# AT89S52.net
KiCad netlist of a schematic drawn in Altium Designer
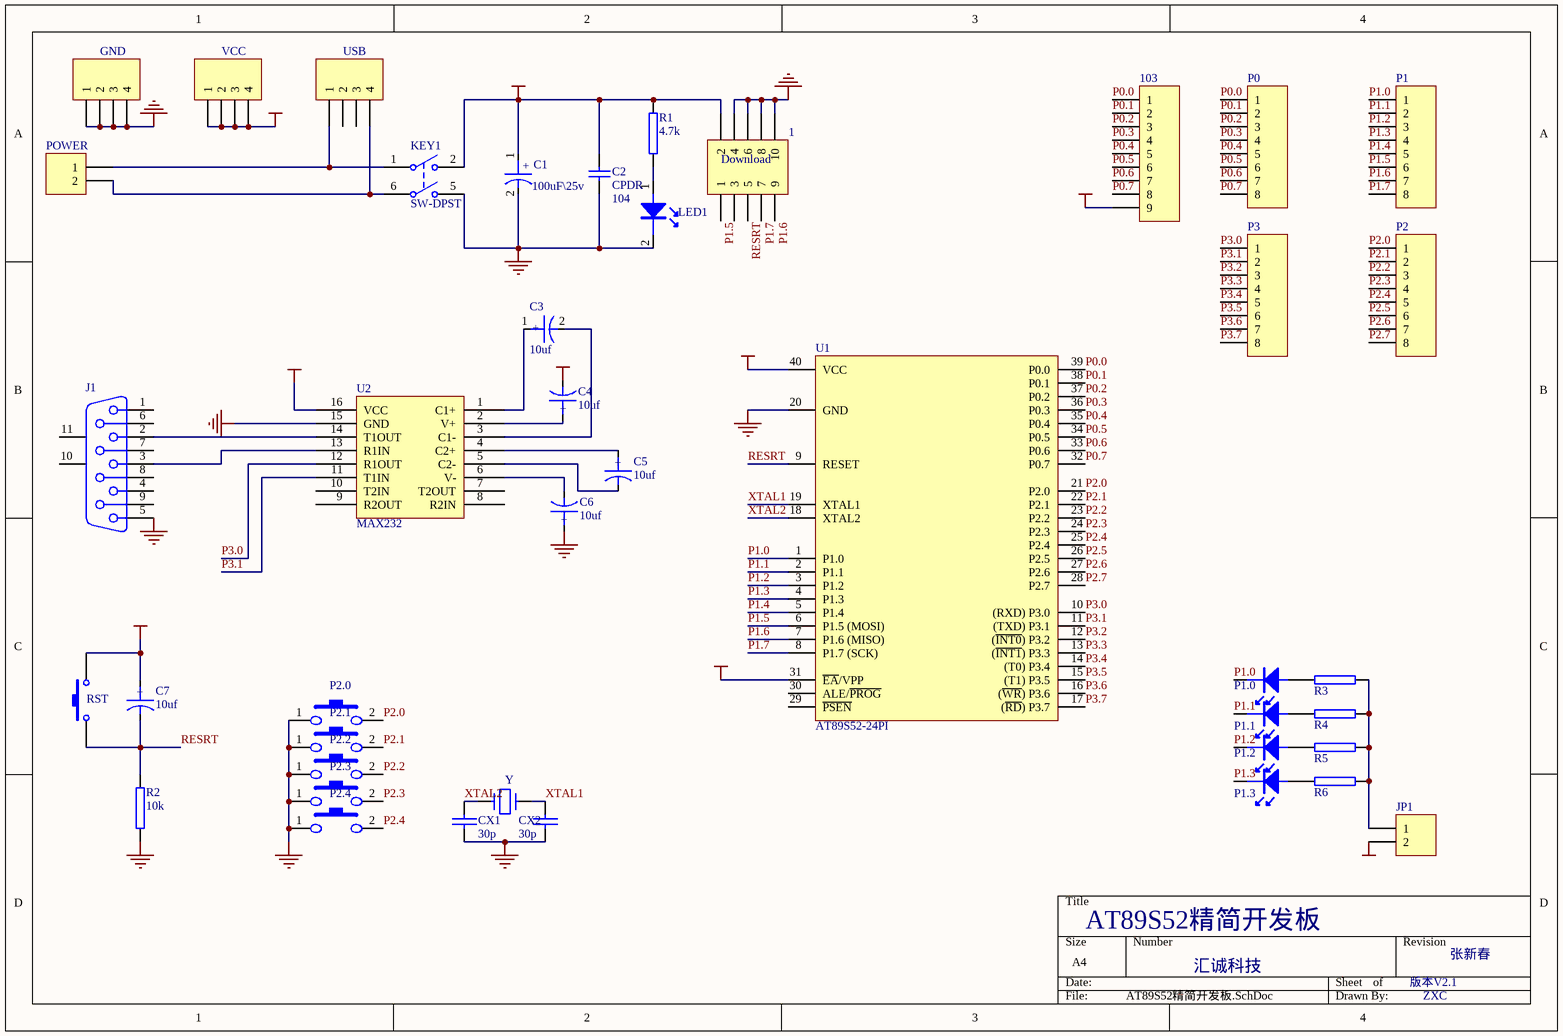
[diagram p0: AT89S52精简开发板.SchDoc]

(export (version "E")
  (design (tool "Eeschema 10.0.6"))
  (components
    (comp (ref "1")
      (value "Download")
      (footprint "HDR-2x5")
      (description "Header, 5-Pin, Dual row")
      (fields (field (name "PUBLISHER") "Altium Limited"))
      (libsource (lib "Miscellaneous Connectors") (part "Header 5X2"))
    )
    (comp (ref "103")
      (value "~")
      (footprint "HDR-9")
      (description "排针——9")
      (fields (field (name "PUBLISHER") "Altium Limited"))
      (libsource (lib "zxcourhc") (part "PZ_9"))
    )
    (comp (ref "C1")
      (value "100u~{F}25v")
      (footprint "C-DJ-6")
      (description "Capacitor")
      (libsource (lib "OldCow1 (1)") (part "CAPACITOR POL"))
    )
    (comp (ref "C2")
      (value "CPDR")
      (footprint "CPDR")
      (description "瓷片电容")
      (fields (field (name "ALTIUM_VALUE") "104") (field (name "PUBLISHER") "Altium Limited"))
      (libsource (lib "zxcourhc") (part "CPDR"))
    )
    (comp (ref "C3")
      (value "10uf")
      (footprint "C-DJ-4")
      (description "Capacitor")
      (libsource (lib "") (part "CAPACITOR POL_1"))
    )
    (comp (ref "C4")
      (value "10uf")
      (footprint "C-DJ-4")
      (description "Capacitor")
      (libsource (lib "*") (part "CAPACITOR POL"))
    )
    (comp (ref "C5")
      (value "10uf")
      (footprint "C-DJ-4")
      (description "Capacitor")
      (libsource (lib "*") (part "CAPACITOR POL"))
    )
    (comp (ref "C6")
      (value "10uf")
      (footprint "C-DJ-4")
      (description "Capacitor")
      (libsource (lib "*") (part "CAPACITOR POL"))
    )
    (comp (ref "C7")
      (value "10uf")
      (footprint "C-DJ-4")
      (description "Capacitor")
      (libsource (lib "*") (part "CAPACITOR POL"))
    )
    (comp (ref "CX1")
      (value "30p")
      (footprint "HDR1X2")
      (description "Capacitor")
      (libsource (lib "*") (part "CAP"))
    )
    (comp (ref "CX2")
      (value "30p")
      (footprint "HDR1X2")
      (description "Capacitor")
      (libsource (lib "*") (part "CAP"))
    )
    (comp (ref "GND")
      (value "~")
      (footprint "HDR1X4")
      (description "Header, 4-Pin")
      (fields (field (name "PUBLISHER") "Altium Limited"))
      (libsource (lib "Miscellaneous Connectors") (part "Header 4"))
    )
    (comp (ref "J1")
      (value "D Connector 9")
      (footprint "DSUB1.385-2H9")
      (description "Receptacle Assembly, 9 Position, Right Angle")
      (fields (field (name "PUBLISHER") "Altium Limited"))
      (libsource (lib "Miscellaneous Connectors") (part "D Connector 9"))
    )
    (comp (ref "JP1")
      (value "~")
      (footprint "HDR1X2")
      (description "Header, 2-Pin")
      (fields (field (name "PUBLISHER") "Altium Limited"))
      (libsource (lib "") (part "Header 2_1"))
    )
    (comp (ref "KEY1")
      (value "SW-DPST")
      (footprint "DPDT-6")
      (description "Double-Pole, Single-Throw Switch")
      (fields (field (name "PUBLISHER") "Altium Limited"))
      (libsource (lib "Miscellaneous Devices") (part "SW-DPST"))
    )
    (comp (ref "LED1") (value "LED") (footprint "LED") (libsource (lib "") (part "LED_1")))
    (comp (ref "P0")
      (value "~")
      (footprint "HDR-8")
      (description "排针——8")
      (fields (field (name "PUBLISHER") "Altium Limited"))
      (libsource (lib "zxcourhc") (part "PZ_8"))
    )
    (comp (ref "P1")
      (value "~")
      (footprint "HDR-8")
      (description "排针——8")
      (fields (field (name "PUBLISHER") "Altium Limited"))
      (libsource (lib "zxcourhc") (part "PZ_8"))
    )
    (comp (ref "P1.0") (value "LED") (footprint "HDR1X2") (libsource (lib "OldCow1 (1)") (part "LED")))
    (comp (ref "P1.1") (value "LED") (footprint "HDR1X2") (libsource (lib "OldCow1 (1)") (part "LED")))
    (comp (ref "P1.2") (value "LED") (footprint "HDR1X2") (libsource (lib "OldCow1 (1)") (part "LED")))
    (comp (ref "P1.3") (value "LED") (footprint "HDR1X2") (libsource (lib "OldCow1 (1)") (part "LED")))
    (comp (ref "P2")
      (value "~")
      (footprint "HDR-8")
      (description "排针——8")
      (fields (field (name "PUBLISHER") "Altium Limited"))
      (libsource (lib "zxcourhc") (part "PZ_8"))
    )
    (comp (ref "P2.0") (value "key1") (footprint "an-6*6") (libsource (lib "OldCow1 (1)") (part "key")))
    (comp (ref "P2.1") (value "key2") (footprint "an-6*6") (libsource (lib "OldCow1 (1)") (part "key")))
    (comp (ref "P2.2") (value "key3") (footprint "an-6*6") (libsource (lib "OldCow1 (1)") (part "key")))
    (comp (ref "P2.3") (value "key4") (footprint "an-6*6") (libsource (lib "OldCow1 (1)") (part "key")))
    (comp (ref "P2.4") (value "key4") (footprint "an-6*6") (libsource (lib "OldCow1 (1)") (part "key")))
    (comp (ref "P3")
      (value "~")
      (footprint "HDR-8")
      (description "排针——8")
      (fields (field (name "PUBLISHER") "Altium Limited"))
      (libsource (lib "zxcourhc") (part "PZ_8"))
    )
    (comp (ref "POWER")
      (value "~")
      (footprint "JK128")
      (description "Header, 2-Pin")
      (fields (field (name "PUBLISHER") "Altium Limited"))
      (libsource (lib "Miscellaneous Connectors") (part "Header 2"))
    )
    (comp (ref "R1") (value "4.7k") (footprint "RSE") (libsource (lib "*") (part "RES2")))
    (comp (ref "R2") (value "10k") (footprint "RSE") (libsource (lib "*") (part "RES2")))
    (comp (ref "R3") (value "470") (footprint "RSE") (libsource (lib "*") (part "RES2")))
    (comp (ref "R4") (value "470") (footprint "RSE") (libsource (lib "*") (part "RES2")))
    (comp (ref "R5") (value "470") (footprint "RSE") (libsource (lib "*") (part "RES2")))
    (comp (ref "R6") (value "470") (footprint "RSE") (libsource (lib "*") (part "RES2")))
    (comp (ref "RST")
      (value "~")
      (footprint "an-6*6")
      (description "Switch")
      (fields (field (name "PUBLISHER") "Altium Limited"))
      (libsource (lib "Miscellaneous Devices") (part "SW-PB"))
    )
    (comp (ref "U1")
      (value "AT89S52-24PI")
      (footprint "DIP-40")
      (description "8 位微处理器/40引脚")
      (fields (field (name "发布者") "磊元工作室"))
      (libsource (lib "MCU") (part "AT89S52-P"))
    )
    (comp (ref "U2") (value "MAX232") (footprint "DIP16") (libsource (lib "*") (part "MAX232")))
    (comp (ref "USB")
      (value "~")
      (footprint "USB-5V")
      (description "Header, 4-Pin")
      (fields (field (name "PUBLISHER") "Altium Limited"))
      (libsource (lib "Miscellaneous Connectors") (part "Header 4"))
    )
    (comp (ref "VCC")
      (value "~")
      (footprint "HDR1X4")
      (description "Header, 4-Pin")
      (fields (field (name "PUBLISHER") "Altium Limited"))
      (libsource (lib "Miscellaneous Connectors") (part "Header 4"))
    )
    (comp (ref "Y1")
      (value "Y")
      (footprint "JZ_ZC")
      (description "Crystal")
      (libsource (lib "*") (part "CRYSTAL"))
    )
  )
  (nets
    (net (code "1") (name "/P0.0") (class "Default")
      (node (ref "103") (pin "1") (pinfunction "1_1") (pintype "passive"))
      (node (ref "P0") (pin "1") (pinfunction "1_1") (pintype "passive"))
      (node (ref "U1") (pin "39") (pinfunction "P0.0_39") (pintype "passive"))
    )
    (net (code "2") (name "/P0.1") (class "Default")
      (node (ref "103") (pin "2") (pinfunction "2_2") (pintype "passive"))
      (node (ref "P0") (pin "2") (pinfunction "2_2") (pintype "passive"))
      (node (ref "U1") (pin "38") (pinfunction "P0.1_38") (pintype "passive"))
    )
    (net (code "3") (name "/P0.2") (class "Default")
      (node (ref "103") (pin "3") (pinfunction "3_3") (pintype "passive"))
      (node (ref "P0") (pin "3") (pinfunction "3_3") (pintype "passive"))
      (node (ref "U1") (pin "37") (pinfunction "P0.2_37") (pintype "passive"))
    )
    (net (code "4") (name "/P0.3") (class "Default")
      (node (ref "103") (pin "4") (pinfunction "4_4") (pintype "passive"))
      (node (ref "P0") (pin "4") (pinfunction "4_4") (pintype "passive"))
      (node (ref "U1") (pin "36") (pinfunction "P0.3_36") (pintype "passive"))
    )
    (net (code "5") (name "/P0.4") (class "Default")
      (node (ref "103") (pin "5") (pinfunction "5_5") (pintype "passive"))
      (node (ref "P0") (pin "5") (pinfunction "5_5") (pintype "passive"))
      (node (ref "U1") (pin "35") (pinfunction "_P0.4_35") (pintype "passive"))
    )
    (net (code "6") (name "/P0.5") (class "Default")
      (node (ref "103") (pin "6") (pinfunction "6_6") (pintype "passive"))
      (node (ref "P0") (pin "6") (pinfunction "6_6") (pintype "passive"))
      (node (ref "U1") (pin "34") (pinfunction "P0.5_34") (pintype "passive"))
    )
    (net (code "7") (name "/P0.6") (class "Default")
      (node (ref "103") (pin "7") (pinfunction "7_7") (pintype "passive"))
      (node (ref "P0") (pin "7") (pinfunction "7_7") (pintype "passive"))
      (node (ref "U1") (pin "33") (pinfunction "P0.6_33") (pintype "passive"))
    )
    (net (code "8") (name "/P0.7") (class "Default")
      (node (ref "103") (pin "8") (pinfunction "8_8") (pintype "passive"))
      (node (ref "P0") (pin "8") (pinfunction "8_8") (pintype "passive"))
      (node (ref "U1") (pin "32") (pinfunction "P0.7_32") (pintype "passive"))
    )
    (net (code "9") (name "/P1.0") (class "Default")
      (node (ref "P1") (pin "1") (pinfunction "1_1") (pintype "passive"))
      (node (ref "P1.0") (pin "2") (pinfunction "K_2") (pintype "passive"))
      (node (ref "U1") (pin "1") (pinfunction "P1.0_1") (pintype "passive"))
    )
    (net (code "10") (name "/P1.1") (class "Default")
      (node (ref "P1") (pin "2") (pinfunction "2_2") (pintype "passive"))
      (node (ref "P1.1") (pin "2") (pinfunction "K_2") (pintype "passive"))
      (node (ref "U1") (pin "2") (pinfunction "P1.1_2") (pintype "passive"))
    )
    (net (code "11") (name "/P1.2") (class "Default")
      (node (ref "P1") (pin "3") (pinfunction "3_3") (pintype "passive"))
      (node (ref "P1.2") (pin "2") (pinfunction "K_2") (pintype "passive"))
      (node (ref "U1") (pin "3") (pinfunction "P1.2_3") (pintype "passive"))
    )
    (net (code "12") (name "/P1.3") (class "Default")
      (node (ref "P1") (pin "4") (pinfunction "4_4") (pintype "passive"))
      (node (ref "P1.3") (pin "2") (pinfunction "K_2") (pintype "passive"))
      (node (ref "U1") (pin "4") (pinfunction "P1.3_4") (pintype "passive"))
    )
    (net (code "13") (name "/P1.4") (class "Default")
      (node (ref "P1") (pin "5") (pinfunction "5_5") (pintype "passive"))
      (node (ref "U1") (pin "5") (pinfunction "P1.4_5") (pintype "passive"))
    )
    (net (code "14") (name "/P1.5") (class "Default")
      (node (ref "1") (pin "1") (pinfunction "1_1") (pintype "passive"))
      (node (ref "P1") (pin "6") (pinfunction "6_6") (pintype "passive"))
      (node (ref "U1") (pin "6") (pinfunction "P1.5_(MOSI)_6") (pintype "passive"))
    )
    (net (code "15") (name "/P1.6") (class "Default")
      (node (ref "1") (pin "9") (pinfunction "9_9") (pintype "passive"))
      (node (ref "P1") (pin "7") (pinfunction "7_7") (pintype "passive"))
      (node (ref "U1") (pin "7") (pinfunction "P1.6_(MISO)_7") (pintype "passive"))
    )
    (net (code "16") (name "/P1.7") (class "Default")
      (node (ref "1") (pin "7") (pinfunction "7_7") (pintype "passive"))
      (node (ref "P1") (pin "8") (pinfunction "8_8") (pintype "passive"))
      (node (ref "U1") (pin "8") (pinfunction "P1.7_(SCK)_8") (pintype "passive"))
    )
    (net (code "17") (name "/P2.0") (class "Default")
      (node (ref "P2") (pin "1") (pinfunction "1_1") (pintype "passive"))
      (node (ref "P2.0") (pin "2") (pinfunction "2_2") (pintype "passive"))
      (node (ref "U1") (pin "21") (pinfunction "P2.0_21") (pintype "passive"))
    )
    (net (code "18") (name "/P2.1") (class "Default")
      (node (ref "P2") (pin "2") (pinfunction "2_2") (pintype "passive"))
      (node (ref "P2.1") (pin "2") (pinfunction "2_2") (pintype "passive"))
      (node (ref "U1") (pin "22") (pinfunction "P2.1_22") (pintype "passive"))
    )
    (net (code "19") (name "/P2.2") (class "Default")
      (node (ref "P2") (pin "3") (pinfunction "3_3") (pintype "passive"))
      (node (ref "P2.2") (pin "2") (pinfunction "2_2") (pintype "passive"))
      (node (ref "U1") (pin "23") (pinfunction "P2.2_23") (pintype "passive"))
    )
    (net (code "20") (name "/P2.3") (class "Default")
      (node (ref "P2") (pin "4") (pinfunction "4_4") (pintype "passive"))
      (node (ref "P2.3") (pin "2") (pinfunction "2_2") (pintype "passive"))
      (node (ref "U1") (pin "24") (pinfunction "P2.3_24") (pintype "passive"))
    )
    (net (code "21") (name "/P2.4") (class "Default")
      (node (ref "P2") (pin "5") (pinfunction "5_5") (pintype "passive"))
      (node (ref "P2.4") (pin "2") (pinfunction "2_2") (pintype "passive"))
      (node (ref "U1") (pin "25") (pinfunction "P2.4_25") (pintype "passive"))
    )
    (net (code "22") (name "/P2.5") (class "Default")
      (node (ref "P2") (pin "6") (pinfunction "6_6") (pintype "passive"))
      (node (ref "U1") (pin "26") (pinfunction "P2.5_26") (pintype "passive"))
    )
    (net (code "23") (name "/P2.6") (class "Default")
      (node (ref "P2") (pin "7") (pinfunction "7_7") (pintype "passive"))
      (node (ref "U1") (pin "27") (pinfunction "P2.6_27") (pintype "passive"))
    )
    (net (code "24") (name "/P2.7") (class "Default")
      (node (ref "P2") (pin "8") (pinfunction "8_8") (pintype "passive"))
      (node (ref "U1") (pin "28") (pinfunction "P2.7_28") (pintype "passive"))
    )
    (net (code "25") (name "/P3.0") (class "Default")
      (node (ref "P3") (pin "1") (pinfunction "1_1") (pintype "passive"))
      (node (ref "U1") (pin "10") (pinfunction "(RXD)_P3.0_10") (pintype "passive"))
      (node (ref "U2") (pin "12") (pinfunction "R1OUT_12") (pintype "passive"))
    )
    (net (code "26") (name "/P3.1") (class "Default")
      (node (ref "P3") (pin "2") (pinfunction "2_2") (pintype "passive"))
      (node (ref "U1") (pin "11") (pinfunction "(TXD)_P3.1_11") (pintype "passive"))
      (node (ref "U2") (pin "11") (pinfunction "T1IN_11") (pintype "passive"))
    )
    (net (code "27") (name "/P3.2") (class "Default")
      (node (ref "P3") (pin "3") (pinfunction "3_3") (pintype "passive"))
      (node (ref "U1") (pin "12") (pinfunction "(~{INT0})_P3.2_12") (pintype "passive"))
    )
    (net (code "28") (name "/P3.3") (class "Default")
      (node (ref "P3") (pin "4") (pinfunction "4_4") (pintype "passive"))
      (node (ref "U1") (pin "13") (pinfunction "(~{INT1})_P3.3_13") (pintype "passive"))
    )
    (net (code "29") (name "/P3.4") (class "Default")
      (node (ref "P3") (pin "5") (pinfunction "5_5") (pintype "passive"))
      (node (ref "U1") (pin "14") (pinfunction "(T0)_P3.4_14") (pintype "passive"))
    )
    (net (code "30") (name "/P3.5") (class "Default")
      (node (ref "P3") (pin "6") (pinfunction "6_6") (pintype "passive"))
      (node (ref "U1") (pin "15") (pinfunction "(T1)_P3.5_15") (pintype "passive"))
    )
    (net (code "31") (name "/P3.6") (class "Default")
      (node (ref "P3") (pin "7") (pinfunction "7_7") (pintype "passive"))
      (node (ref "U1") (pin "16") (pinfunction "(~{WR})_P3.6_16") (pintype "passive"))
    )
    (net (code "32") (name "/P3.7") (class "Default")
      (node (ref "P3") (pin "8") (pinfunction "8_8") (pintype "passive"))
      (node (ref "U1") (pin "17") (pinfunction "(~{RD})_P3.7_17") (pintype "passive"))
    )
    (net (code "33") (name "/RESRT") (class "Default")
      (node (ref "1") (pin "5") (pinfunction "5_5") (pintype "passive"))
      (node (ref "C7") (pin "2") (pinfunction "2_2") (pintype "passive"))
      (node (ref "R2") (pin "2") (pinfunction "2_2") (pintype "passive"))
      (node (ref "RST") (pin "2") (pinfunction "2_2") (pintype "passive"))
      (node (ref "U1") (pin "9") (pinfunction "RESET_9") (pintype "passive"))
    )
    (net (code "34") (name "/XTAL1") (class "Default")
      (node (ref "CX2") (pin "1") (pinfunction "1_1") (pintype "passive"))
      (node (ref "U1") (pin "19") (pinfunction "XTAL1_19") (pintype "passive"))
      (node (ref "Y1") (pin "1") (pinfunction "1_1") (pintype "passive"))
    )
    (net (code "35") (name "/XTAL2") (class "Default")
      (node (ref "CX1") (pin "1") (pinfunction "1_1") (pintype "passive"))
      (node (ref "U1") (pin "18") (pinfunction "XTAL2_18") (pintype "passive"))
      (node (ref "Y1") (pin "2") (pinfunction "2_2") (pintype "passive"))
    )
    (net (code "36") (name "GND") (class "Default")
      (node (ref "1") (pin "10") (pinfunction "10_10") (pintype "passive"))
      (node (ref "1") (pin "4") (pinfunction "4_4") (pintype "passive"))
      (node (ref "1") (pin "6") (pinfunction "6_6") (pintype "passive"))
      (node (ref "1") (pin "8") (pinfunction "8_8") (pintype "passive"))
      (node (ref "C1") (pin "2") (pinfunction "2_2") (pintype "passive"))
      (node (ref "C2") (pin "1") (pinfunction "1_1") (pintype "passive"))
      (node (ref "C6") (pin "1") (pinfunction "1_1") (pintype "passive"))
      (node (ref "CX1") (pin "2") (pinfunction "2_2") (pintype "passive"))
      (node (ref "CX2") (pin "2") (pinfunction "2_2") (pintype "passive"))
      (node (ref "GND") (pin "1") (pinfunction "1_1") (pintype "passive"))
      (node (ref "GND") (pin "2") (pinfunction "2_2") (pintype "passive"))
      (node (ref "GND") (pin "3") (pinfunction "3_3") (pintype "passive"))
      (node (ref "GND") (pin "4") (pinfunction "4_4") (pintype "passive"))
      (node (ref "J1") (pin "5") (pinfunction "5_5") (pintype "passive"))
      (node (ref "KEY1") (pin "5") (pinfunction "NO2_5") (pintype "passive"))
      (node (ref "LED1") (pin "2") (pinfunction "K_2") (pintype "passive"))
      (node (ref "P2.0") (pin "1") (pinfunction "1_1") (pintype "passive"))
      (node (ref "P2.1") (pin "1") (pinfunction "1_1") (pintype "passive"))
      (node (ref "P2.2") (pin "1") (pinfunction "1_1") (pintype "passive"))
      (node (ref "P2.3") (pin "1") (pinfunction "1_1") (pintype "passive"))
      (node (ref "P2.4") (pin "1") (pinfunction "1_1") (pintype "passive"))
      (node (ref "R2") (pin "1") (pinfunction "1_1") (pintype "passive"))
      (node (ref "U1") (pin "20") (pinfunction "GND_20") (pintype "power_in"))
      (node (ref "U2") (pin "15") (pinfunction "GND_15") (pintype "passive"))
    )
    (net (code "37") (name "Net-(JP1-Pad1)") (class "Default")
      (node (ref "JP1") (pin "1") (pinfunction "1_1") (pintype "passive"))
      (node (ref "R3") (pin "1") (pinfunction "1_1") (pintype "passive"))
      (node (ref "R4") (pin "1") (pinfunction "1_1") (pintype "passive"))
      (node (ref "R5") (pin "1") (pinfunction "1_1") (pintype "passive"))
      (node (ref "R6") (pin "1") (pinfunction "1_1") (pintype "passive"))
    )
    (net (code "38") (name "Net-(KEY1-COMMON1)") (class "Default")
      (node (ref "KEY1") (pin "1") (pinfunction "COMMON1_1") (pintype "passive"))
      (node (ref "POWER") (pin "1") (pinfunction "1_1") (pintype "passive"))
      (node (ref "USB") (pin "1") (pinfunction "1_1") (pintype "passive"))
    )
    (net (code "39") (name "Net-(KEY1-COMMON2)") (class "Default")
      (node (ref "KEY1") (pin "6") (pinfunction "COMMON2_6") (pintype "passive"))
      (node (ref "POWER") (pin "2") (pinfunction "2_2") (pintype "passive"))
      (node (ref "USB") (pin "4") (pinfunction "4_4") (pintype "passive"))
    )
    (net (code "40") (name "Net-(LED1-A)") (class "Default")
      (node (ref "LED1") (pin "1") (pinfunction "A_1") (pintype "passive"))
      (node (ref "R1") (pin "2") (pinfunction "2_2") (pintype "passive"))
    )
    (net (code "41") (name "Net-(P1.0-A)") (class "Default")
      (node (ref "P1.0") (pin "1") (pinfunction "A_1") (pintype "passive"))
      (node (ref "R3") (pin "2") (pinfunction "2_2") (pintype "passive"))
    )
    (net (code "42") (name "Net-(P1.1-A)") (class "Default")
      (node (ref "P1.1") (pin "1") (pinfunction "A_1") (pintype "passive"))
      (node (ref "R4") (pin "2") (pinfunction "2_2") (pintype "passive"))
    )
    (net (code "43") (name "Net-(P1.2-A)") (class "Default")
      (node (ref "P1.2") (pin "1") (pinfunction "A_1") (pintype "passive"))
      (node (ref "R5") (pin "2") (pinfunction "2_2") (pintype "passive"))
    )
    (net (code "44") (name "Net-(P1.3-A)") (class "Default")
      (node (ref "P1.3") (pin "1") (pinfunction "A_1") (pintype "passive"))
      (node (ref "R6") (pin "2") (pinfunction "2_2") (pintype "passive"))
    )
    (net (code "45") (name "Net-(U2-C1+)") (class "Default")
      (node (ref "C3") (pin "1") (pinfunction "1_1") (pintype "passive"))
      (node (ref "U2") (pin "1") (pinfunction "C1+_1") (pintype "passive"))
    )
    (net (code "46") (name "Net-(U2-C1-)") (class "Default")
      (node (ref "C3") (pin "2") (pinfunction "2_2") (pintype "passive"))
      (node (ref "U2") (pin "3") (pinfunction "C1-_3") (pintype "passive"))
    )
    (net (code "47") (name "Net-(U2-C2+)") (class "Default")
      (node (ref "C5") (pin "1") (pinfunction "1_1") (pintype "passive"))
      (node (ref "U2") (pin "4") (pinfunction "C2+_4") (pintype "passive"))
    )
    (net (code "48") (name "Net-(U2-C2-)") (class "Default")
      (node (ref "C5") (pin "2") (pinfunction "2_2") (pintype "passive"))
      (node (ref "U2") (pin "5") (pinfunction "C2-_5") (pintype "passive"))
    )
    (net (code "49") (name "Net-(U2-R1IN)") (class "Default")
      (node (ref "J1") (pin "3") (pinfunction "3_3") (pintype "passive"))
      (node (ref "U2") (pin "13") (pinfunction "R1IN_13") (pintype "passive"))
    )
    (net (code "50") (name "Net-(U2-T1OUT)") (class "Default")
      (node (ref "J1") (pin "2") (pinfunction "2_2") (pintype "passive"))
      (node (ref "U2") (pin "14") (pinfunction "T1OUT_14") (pintype "passive"))
    )
    (net (code "51") (name "Net-(U2-V+)") (class "Default")
      (node (ref "C4") (pin "1") (pinfunction "1_1") (pintype "passive"))
      (node (ref "U2") (pin "2") (pinfunction "V+_2") (pintype "passive"))
    )
    (net (code "52") (name "Net-(U2-V-)") (class "Default")
      (node (ref "C6") (pin "2") (pinfunction "2_2") (pintype "passive"))
      (node (ref "U2") (pin "6") (pinfunction "V-_6") (pintype "passive"))
    )
    (net (code "53") (name "VCC") (class "Default")
      (node (ref "1") (pin "2") (pinfunction "2_2") (pintype "passive"))
      (node (ref "103") (pin "9") (pinfunction "9_9") (pintype "passive"))
      (node (ref "C1") (pin "1") (pinfunction "1_1") (pintype "passive"))
      (node (ref "C2") (pin "2") (pinfunction "2_2") (pintype "passive"))
      (node (ref "C4") (pin "2") (pinfunction "2_2") (pintype "passive"))
      (node (ref "C7") (pin "1") (pinfunction "1_1") (pintype "passive"))
      (node (ref "JP1") (pin "2") (pinfunction "2_2") (pintype "passive"))
      (node (ref "KEY1") (pin "2") (pinfunction "NO1_2") (pintype "passive"))
      (node (ref "R1") (pin "1") (pinfunction "1_1") (pintype "passive"))
      (node (ref "RST") (pin "1") (pinfunction "1_1") (pintype "passive"))
      (node (ref "U1") (pin "31") (pinfunction "~{EA}/VPP_31") (pintype "passive"))
      (node (ref "U1") (pin "40") (pinfunction "VCC_40") (pintype "power_in"))
      (node (ref "U2") (pin "16") (pinfunction "VCC_16") (pintype "passive"))
      (node (ref "VCC") (pin "1") (pinfunction "1_1") (pintype "passive"))
      (node (ref "VCC") (pin "2") (pinfunction "2_2") (pintype "passive"))
      (node (ref "VCC") (pin "3") (pinfunction "3_3") (pintype "passive"))
      (node (ref "VCC") (pin "4") (pinfunction "4_4") (pintype "passive"))
    )
    (net (code "54") (name "unconnected-(1-Pad3)") (class "Default")
      (node (ref "1") (pin "3") (pinfunction "3_3") (pintype "passive"))
    )
    (net (code "55") (name "unconnected-(J1-MH1-Pad10)") (class "Default")
      (node (ref "J1") (pin "10") (pinfunction "MH1_10") (pintype "passive"))
    )
    (net (code "56") (name "unconnected-(J1-MH2-Pad11)") (class "Default")
      (node (ref "J1") (pin "11") (pinfunction "MH2_11") (pintype "passive"))
    )
    (net (code "57") (name "unconnected-(J1-Pad1)") (class "Default")
      (node (ref "J1") (pin "1") (pinfunction "1_1") (pintype "passive"))
    )
    (net (code "58") (name "unconnected-(J1-Pad4)") (class "Default")
      (node (ref "J1") (pin "4") (pinfunction "4_4") (pintype "passive"))
    )
    (net (code "59") (name "unconnected-(J1-Pad6)") (class "Default")
      (node (ref "J1") (pin "6") (pinfunction "6_6") (pintype "passive"))
    )
    (net (code "60") (name "unconnected-(J1-Pad7)") (class "Default")
      (node (ref "J1") (pin "7") (pinfunction "7_7") (pintype "passive"))
    )
    (net (code "61") (name "unconnected-(J1-Pad8)") (class "Default")
      (node (ref "J1") (pin "8") (pinfunction "8_8") (pintype "passive"))
    )
    (net (code "62") (name "unconnected-(J1-Pad9)") (class "Default")
      (node (ref "J1") (pin "9") (pinfunction "9_9") (pintype "passive"))
    )
    (net (code "63") (name "unconnected-(U1-ALE{slash}~{PROG}-Pad30)") (class "Default")
      (node (ref "U1") (pin "30") (pinfunction "ALE/~{PROG}_30") (pintype "passive"))
    )
    (net (code "64") (name "unconnected-(U1-~{PSEN}-Pad29)") (class "Default")
      (node (ref "U1") (pin "29") (pinfunction "~{PSEN}_29") (pintype "passive"))
    )
    (net (code "65") (name "unconnected-(U2-R2IN-Pad8)") (class "Default")
      (node (ref "U2") (pin "8") (pinfunction "R2IN_8") (pintype "passive"))
    )
    (net (code "66") (name "unconnected-(U2-R2OUT-Pad9)") (class "Default")
      (node (ref "U2") (pin "9") (pinfunction "R2OUT_9") (pintype "passive"))
    )
    (net (code "67") (name "unconnected-(U2-T2IN-Pad10)") (class "Default")
      (node (ref "U2") (pin "10") (pinfunction "T2IN_10") (pintype "passive"))
    )
    (net (code "68") (name "unconnected-(U2-T2OUT-Pad7)") (class "Default")
      (node (ref "U2") (pin "7") (pinfunction "T2OUT_7") (pintype "passive"))
    )
    (net (code "69") (name "unconnected-(USB-Pad2)") (class "Default")
      (node (ref "USB") (pin "2") (pinfunction "2_2") (pintype "passive"))
    )
    (net (code "70") (name "unconnected-(USB-Pad3)") (class "Default")
      (node (ref "USB") (pin "3") (pinfunction "3_3") (pintype "passive"))
    )
  )
)
